# Hutschienenmoped_24V.net
KiCad netlist of a schematic drawn in EAGLE
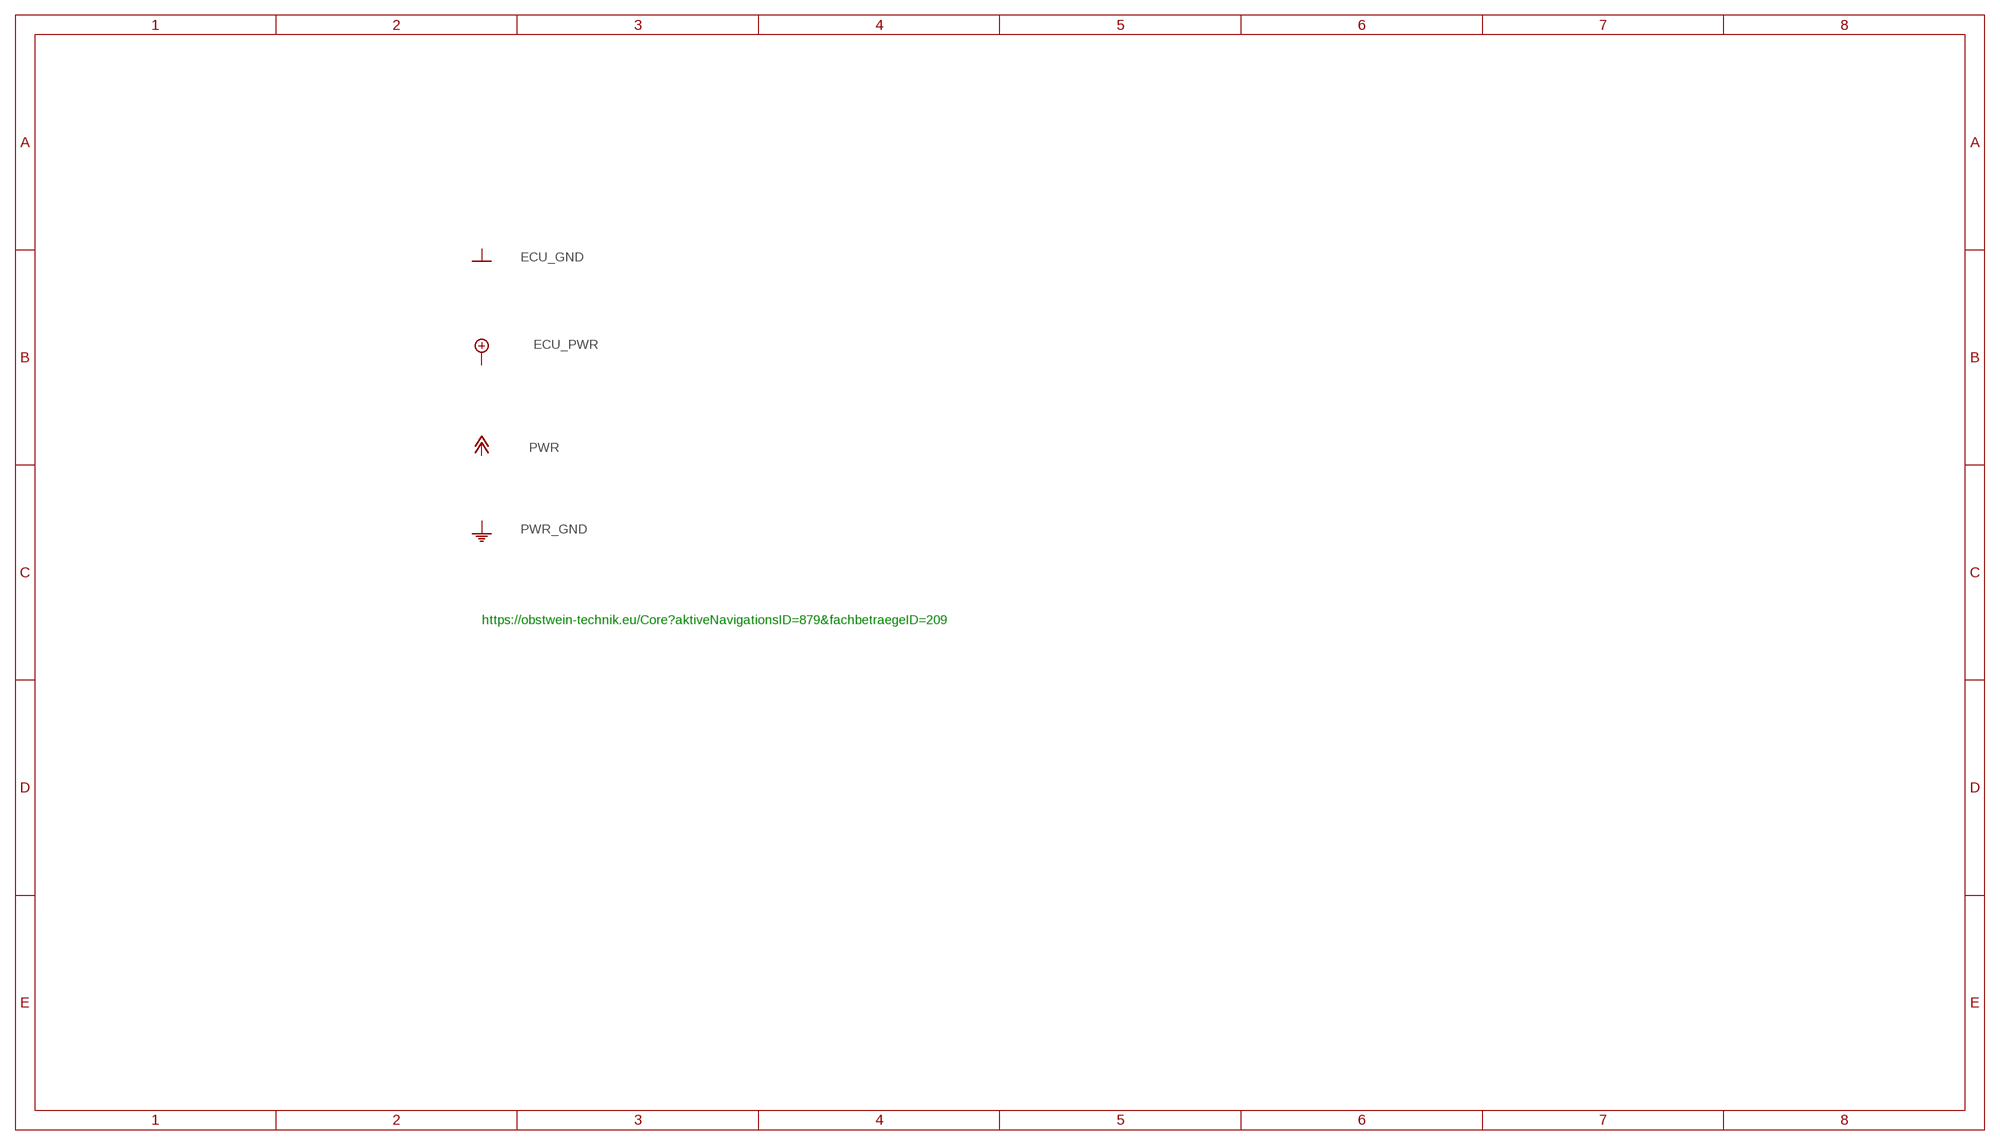
[diagram p0: schematic, sheet 1]
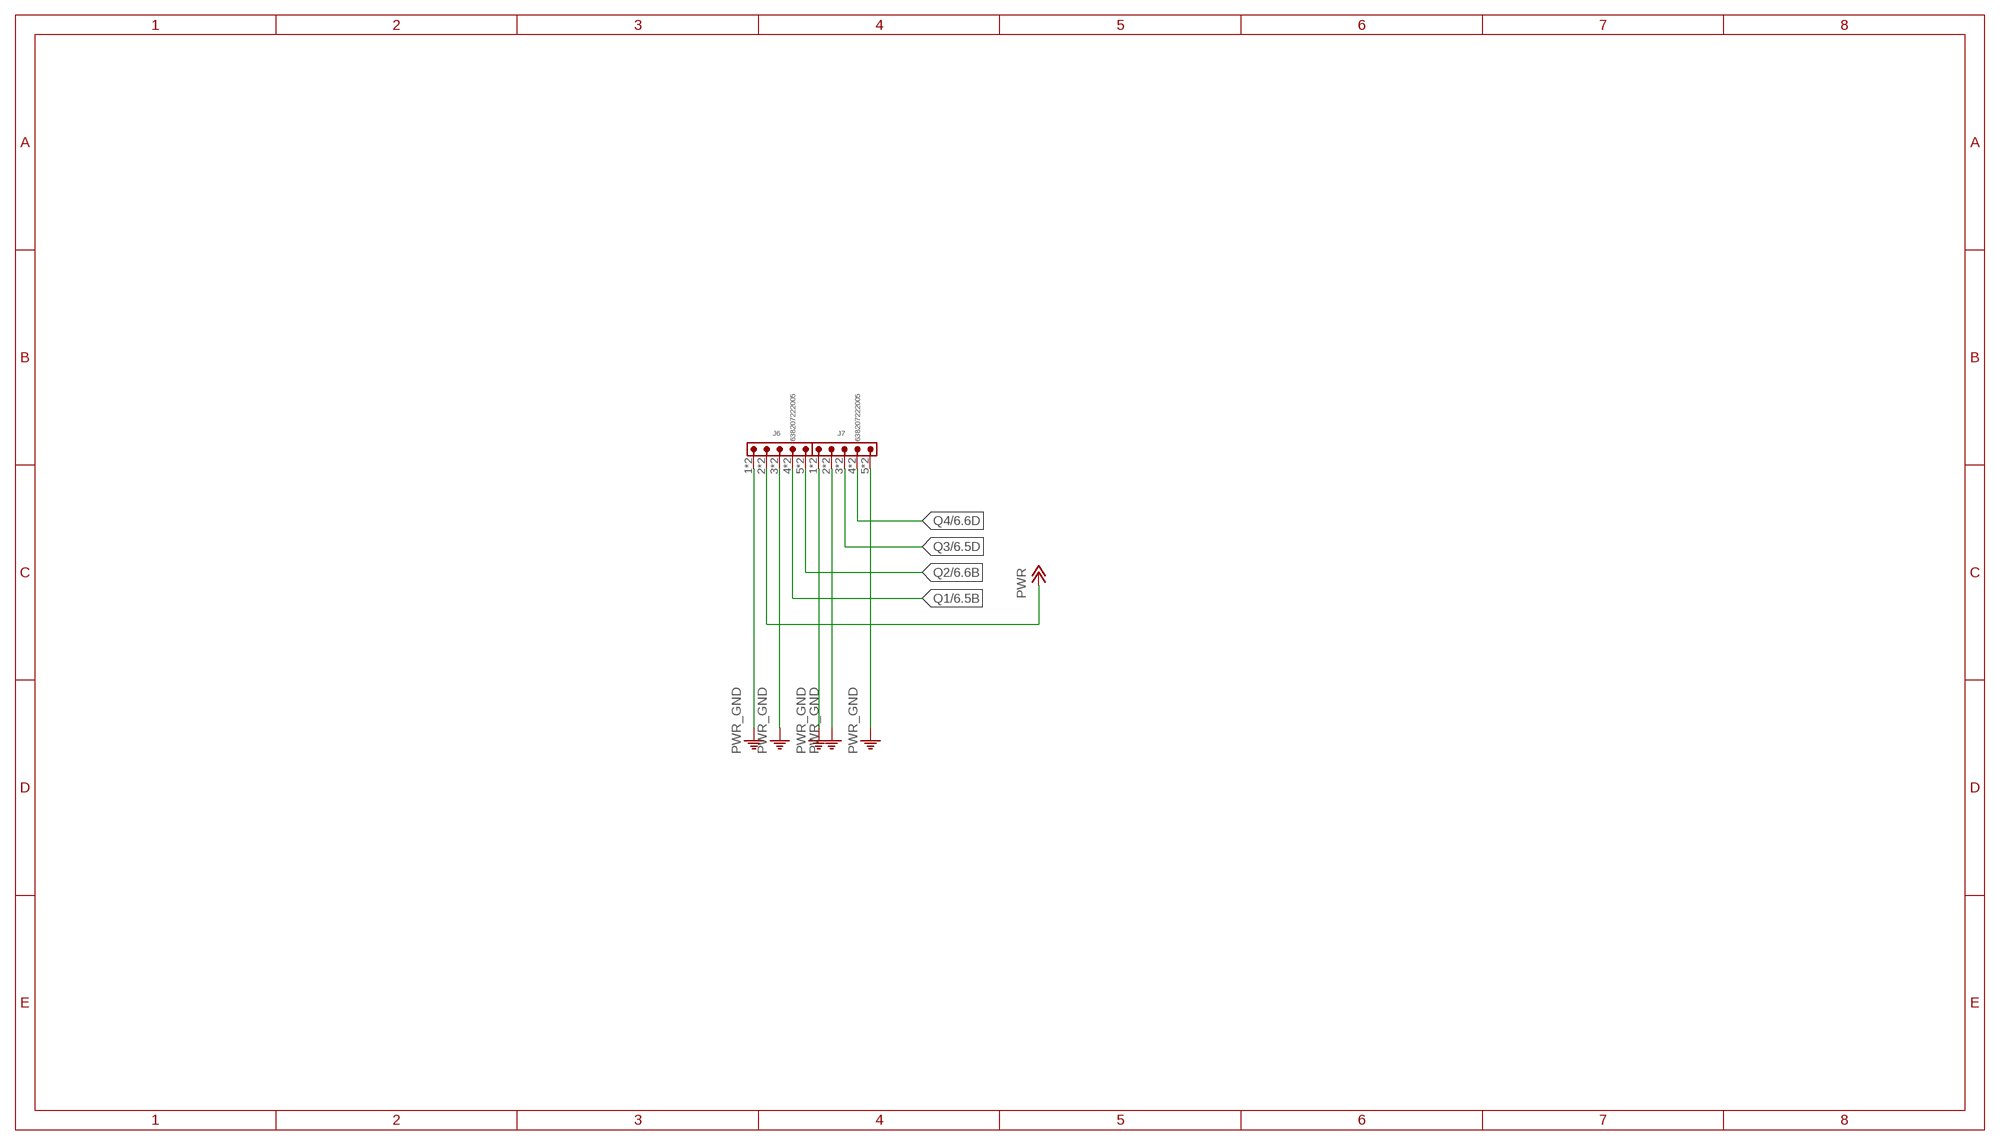
[diagram p1: schematic, sheet 2]
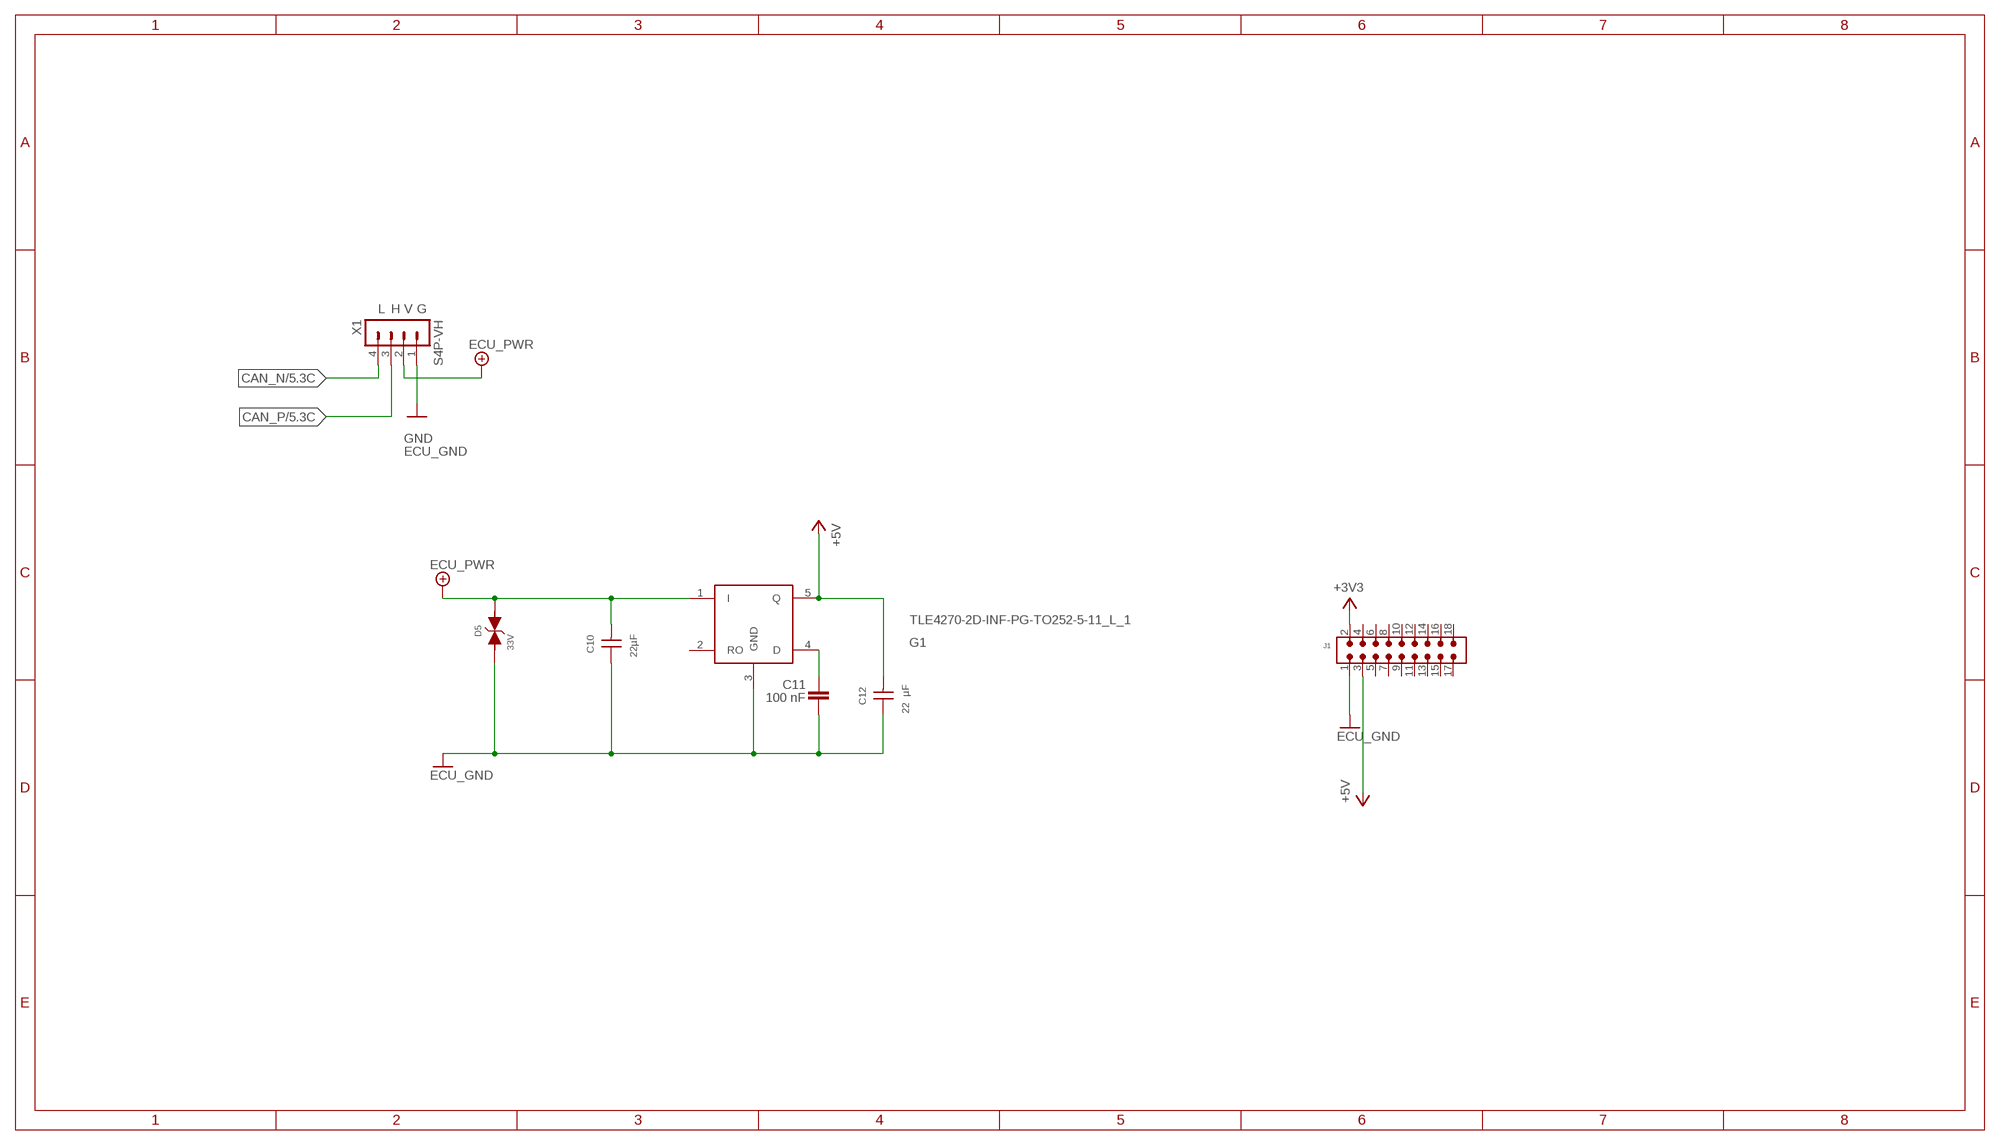
[diagram p2: schematic, sheet 3]
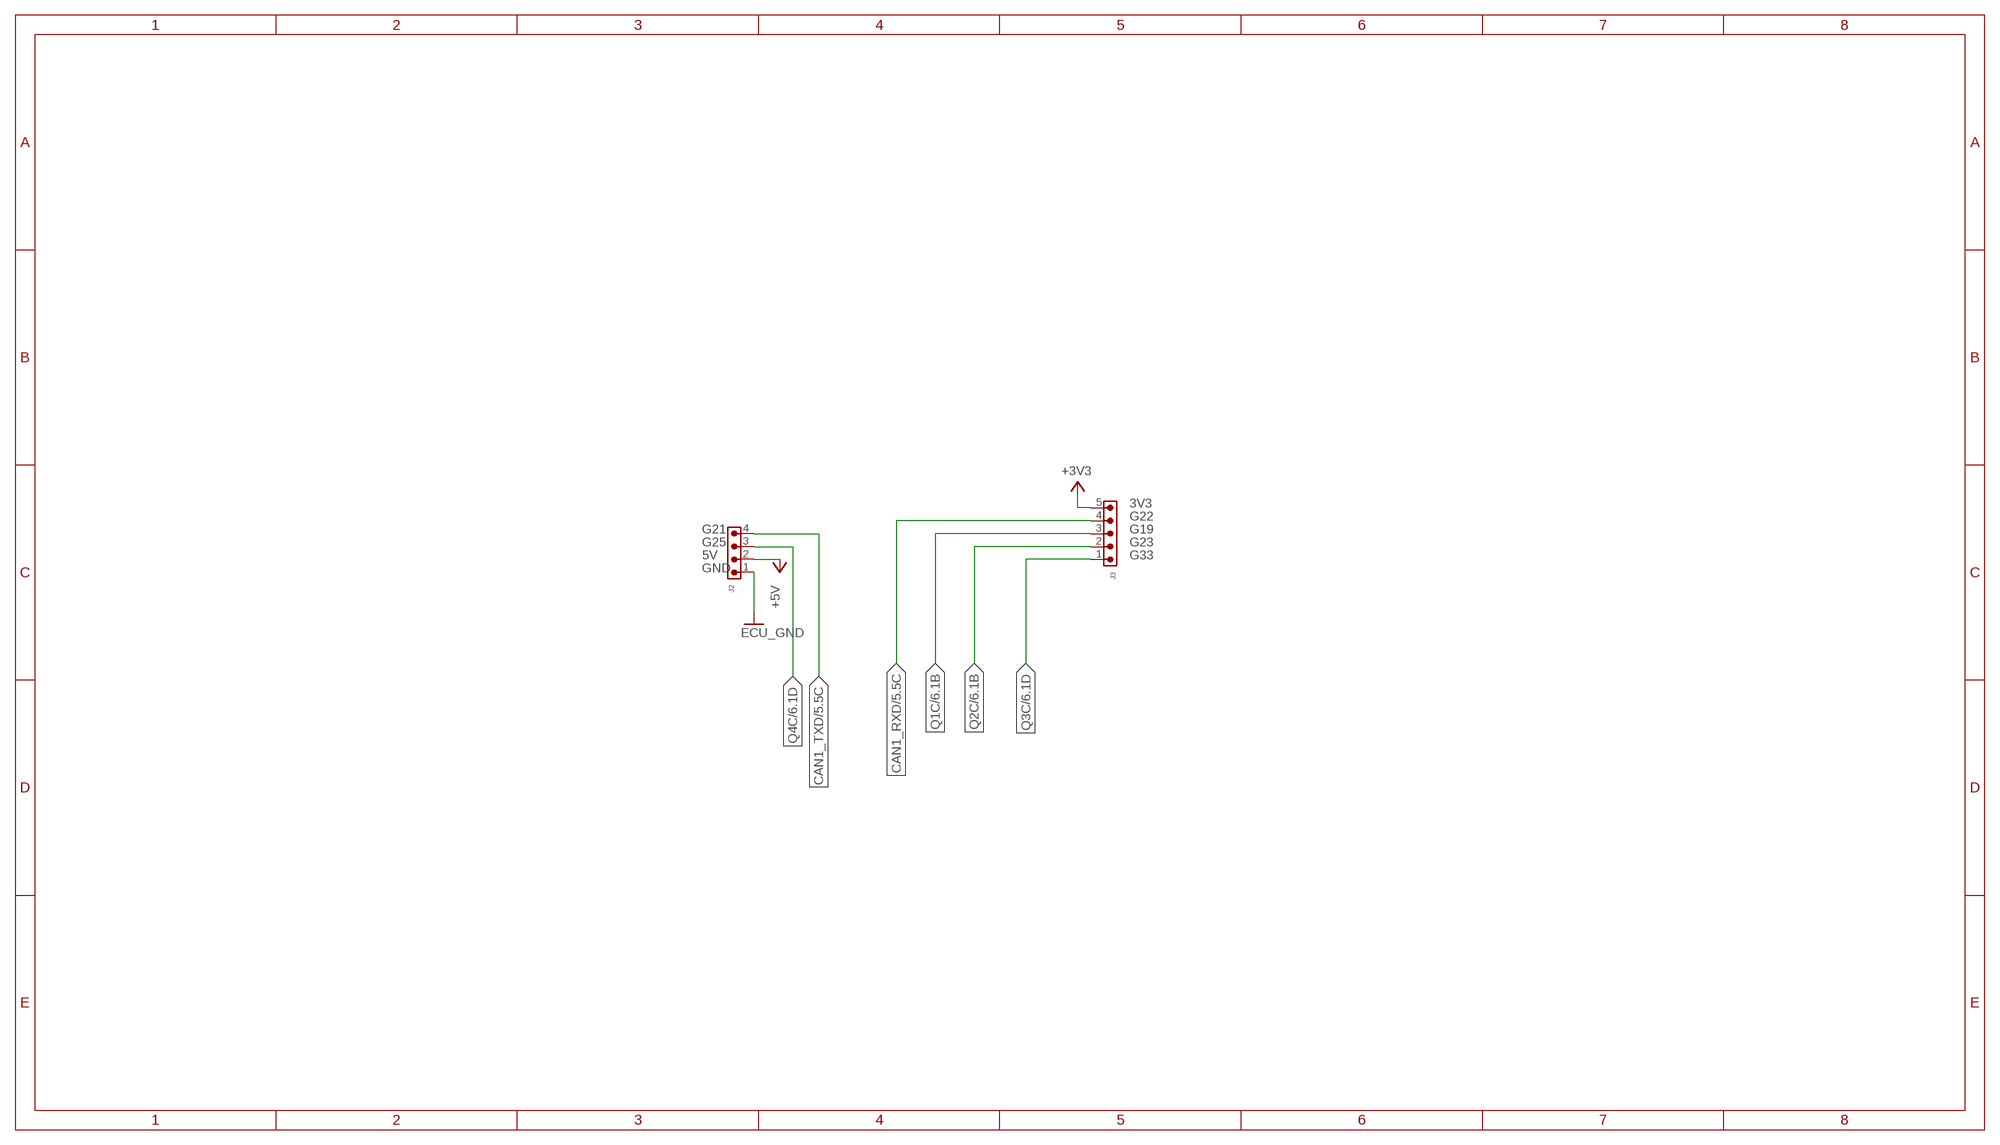
[diagram p3: schematic, sheet 4]
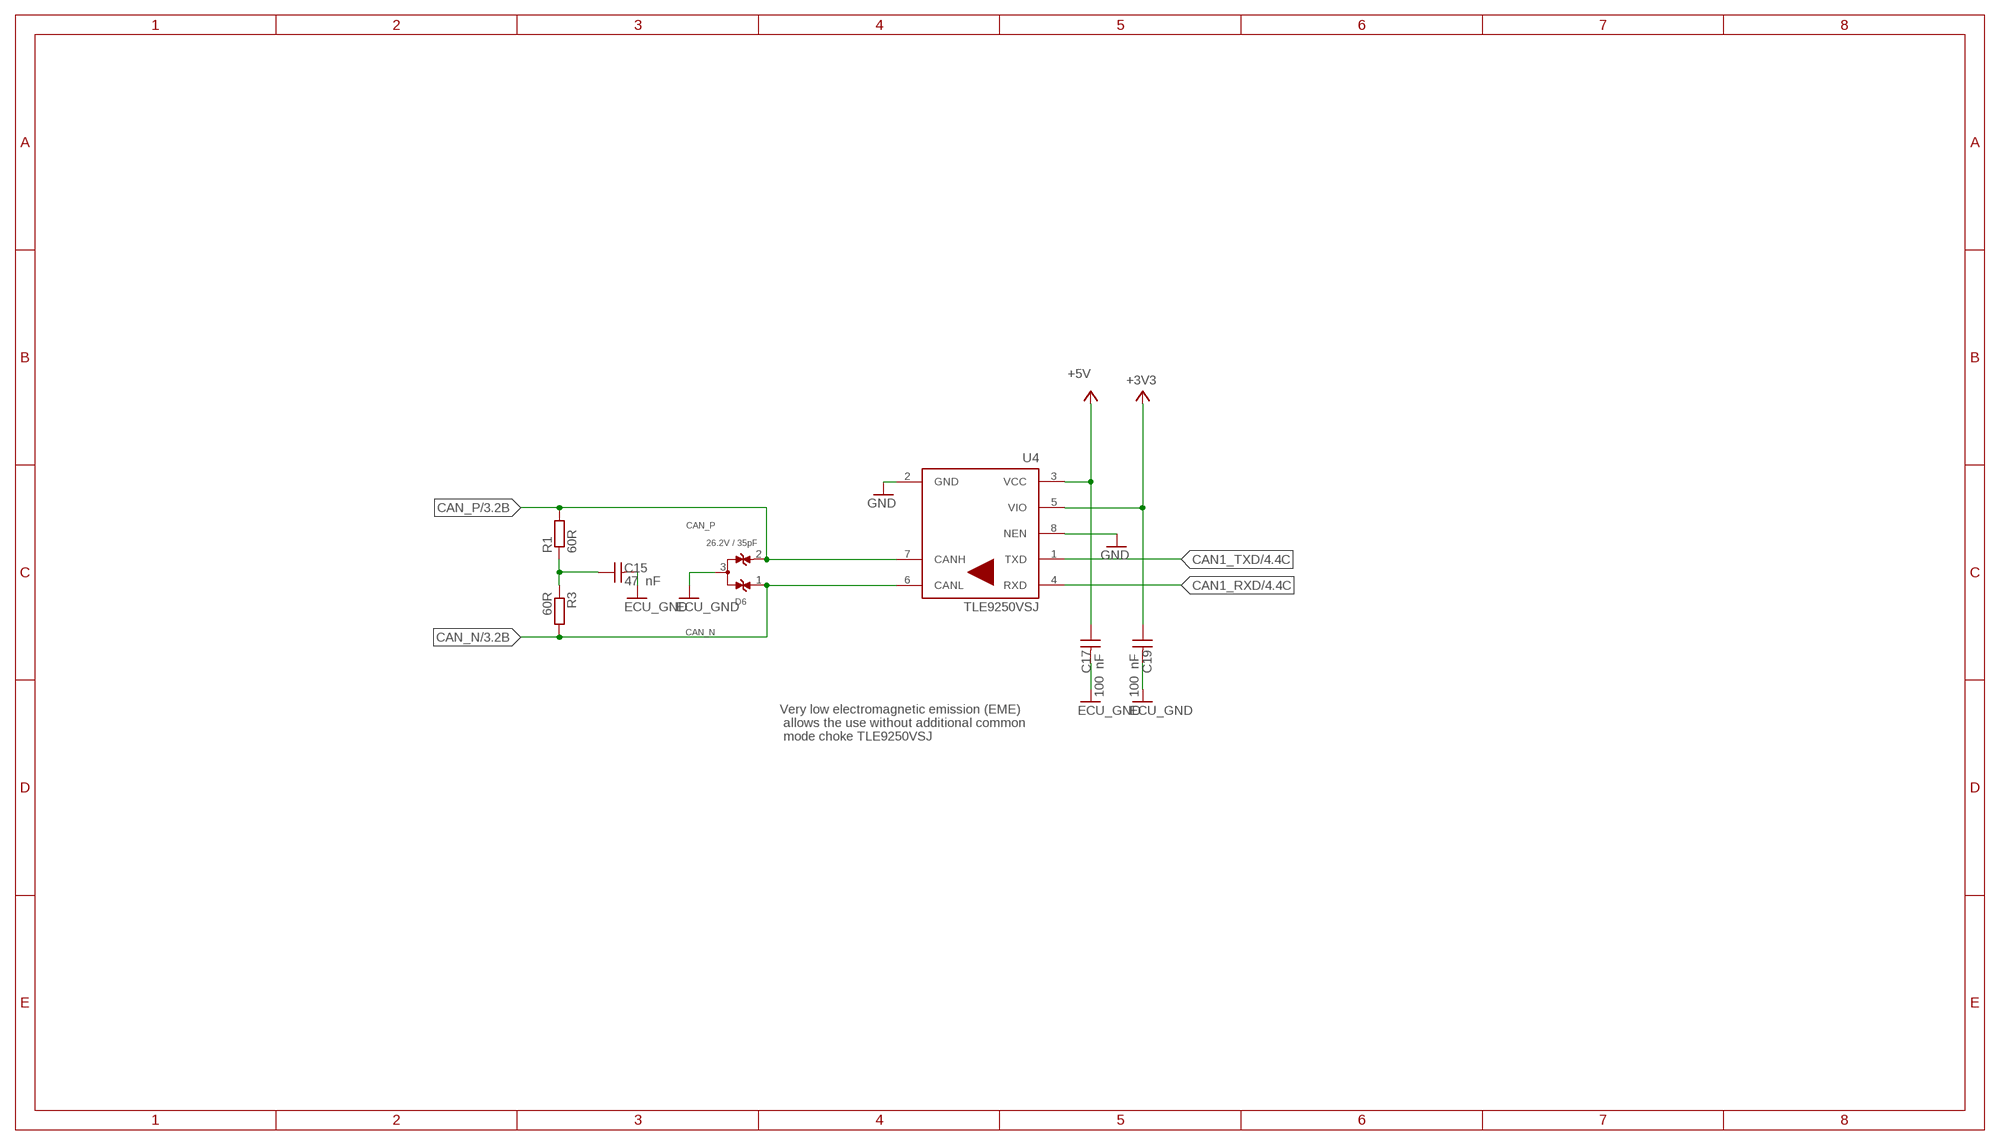
[diagram p4: schematic, sheet 5]
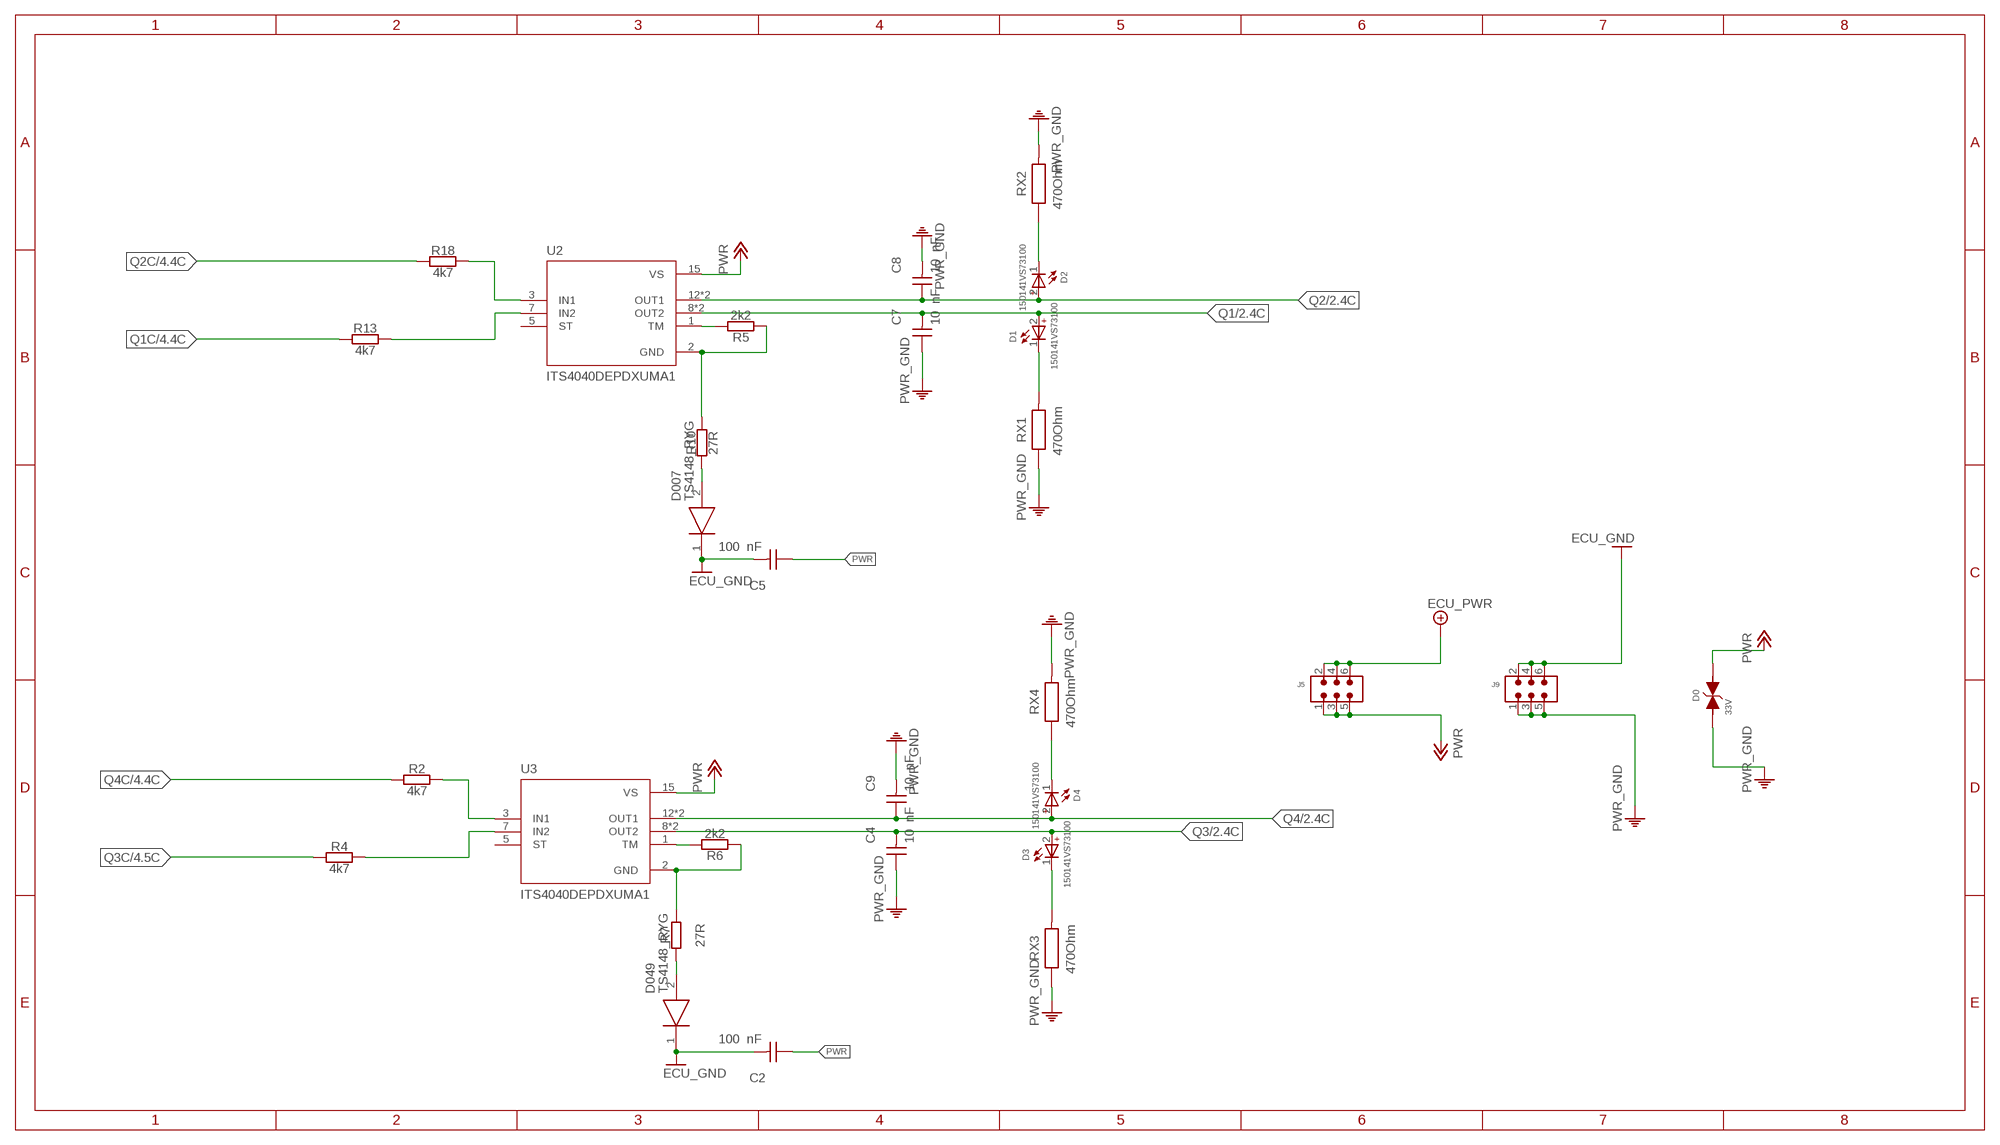
[diagram p5: schematic, sheet 6]

(export (version "E")
  (design (tool "Eeschema 10.0.6"))
  (components
    (comp (ref "C10")
      (value "22µF")
      (footprint "eagle-import:WCAP-CSGP_1210_H2.5")
      (libsource (lib "eagle-import") (part "WCAP-CSGP_1210_H2.5_25V(DC)_885012109014"))
    )
    (comp (ref "C11")
      (value "100 nF")
      (footprint "eagle-import:WCAP-CSGP_0402")
      (libsource (lib "eagle-import") (part "WCAP-CSGP_0402_16V(DC)_885012205037"))
    )
    (comp (ref "C12")
      (value "22 µF")
      (footprint "eagle-import:WCAP-CSGP_0805_H1.25_R")
      (libsource (lib "eagle-import") (part "WCAP-CSGP_0805_H1.25_10V(DC)_885012107011"))
    )
    (comp (ref "D5")
      (value "33V")
      (footprint "eagle-import:WE-TVSP_DO-214AB_BIDIRECTIONAL")
      (libsource (lib "eagle-import") (part "WE-TVSP_DO-214AB_3000W_BI_824551331"))
    )
    (comp (ref "G1")
      (value "TLE4270-2D-INF-PG-TO252-5-11_L_1")
      (footprint "eagle-import:INF-PG-TO252-5-11_L_1PRIMARY")
      (libsource (lib "eagle-import") (part "TLE4270-2D-INF-PG-TO252-5-11_L_1"))
    )
    (comp (ref "J1")
      (value "6130XX21121_61301821121")
      (footprint "eagle-import:61301821121")
      (libsource (lib "eagle-import") (part "6130XX21121_61301821121"))
    )
    (comp (ref "X1")
      (value "S4P-VH")
      (footprint "eagle-import:S4P-VH")
      (libsource (lib "eagle-import") (part "S4P-VH"))
    )
    (comp (ref "J2")
      (value "6130XX11121_61300411121")
      (footprint "eagle-import:61300411121")
      (libsource (lib "eagle-import") (part "6130XX11121_61300411121"))
    )
    (comp (ref "J3")
      (value "6130XX11121_61300511121")
      (footprint "eagle-import:61300511121")
      (libsource (lib "eagle-import") (part "6130XX11121_61300511121"))
    )
    (comp (ref "C15")
      (value "47 nF")
      (footprint "eagle-import:WCAP-CSGP_0805_H0.8_R")
      (libsource (lib "eagle-import") (part "WCAP-CSGP_0805_H0.8_50V(DC)_R_885012207096"))
    )
    (comp (ref "C17")
      (value "100 nF")
      (footprint "eagle-import:WCAP-CSGP_0805_H0.8_R")
      (libsource (lib "eagle-import") (part "WCAP-CSGP_0805_H0.8_50V(DC)_R_885012207098"))
    )
    (comp (ref "C19")
      (value "100 nF")
      (footprint "eagle-import:WCAP-CSGP_0805_H0.8_R")
      (libsource (lib "eagle-import") (part "WCAP-CSGP_0805_H0.8_50V(DC)_R_885012207098"))
    )
    (comp (ref "D6")
      (value "26.2V / 35pF")
      (footprint "eagle-import:WE-TVS_SOT23-3L")
      (libsource (lib "eagle-import") (part "WE-TVS_SOT23-3L_824098024"))
    )
    (comp (ref "R1")
      (value "60R")
      (footprint "eagle-import:R0805")
      (libsource (lib "eagle-import") (part "R-EU_R0805"))
    )
    (comp (ref "R3")
      (value "60R")
      (footprint "eagle-import:R0805")
      (libsource (lib "eagle-import") (part "R-EU_R0805"))
    )
    (comp (ref "U4")
      (value "TLE9250VSJ")
      (footprint "eagle-import:SOIC127P602X173-8N-V")
      (libsource (lib "eagle-import") (part "TLE9250VSJ"))
    )
    (comp (ref "C2")
      (value "100 nF")
      (footprint "eagle-import:WCAP-CSGP_0805_H0.8_R")
      (libsource (lib "eagle-import") (part "WCAP-CSGP_0805_H0.8_50V(DC)_R_885012207098"))
    )
    (comp (ref "C4")
      (value "10 nF")
      (footprint "eagle-import:WCAP-CSGP_0805_H0.8_R")
      (libsource (lib "eagle-import") (part "WCAP-CSGP_0805_H0.8_50V(DC)_R_885012207092"))
    )
    (comp (ref "C5")
      (value "100 nF")
      (footprint "eagle-import:WCAP-CSGP_0805_H0.8_R")
      (libsource (lib "eagle-import") (part "WCAP-CSGP_0805_H0.8_50V(DC)_R_885012207098"))
    )
    (comp (ref "C7")
      (value "10 nF")
      (footprint "eagle-import:WCAP-CSGP_0805_H0.8_R")
      (libsource (lib "eagle-import") (part "WCAP-CSGP_0805_H0.8_50V(DC)_R_885012207092"))
    )
    (comp (ref "C8")
      (value "10 nF")
      (footprint "eagle-import:WCAP-CSGP_0805_H0.8_R")
      (libsource (lib "eagle-import") (part "WCAP-CSGP_0805_H0.8_50V(DC)_R_885012207092"))
    )
    (comp (ref "C9")
      (value "10 nF")
      (footprint "eagle-import:WCAP-CSGP_0805_H0.8_R")
      (libsource (lib "eagle-import") (part "WCAP-CSGP_0805_H0.8_50V(DC)_R_885012207092"))
    )
    (comp (ref "D0")
      (value "33V")
      (footprint "eagle-import:WE-TVSP_DO-214AB_BIDIRECTIONAL")
      (libsource (lib "eagle-import") (part "WE-TVSP_DO-214AB_3000W_BI_824551331"))
    )
    (comp (ref "D1")
      (value "150141VS73100")
      (footprint "eagle-import:WL-SMTW_3528")
      (libsource (lib "eagle-import") (part "WL-SMTW_3528_150141VS73100"))
    )
    (comp (ref "D2")
      (value "150141VS73100")
      (footprint "eagle-import:WL-SMTW_3528")
      (libsource (lib "eagle-import") (part "WL-SMTW_3528_150141VS73100"))
    )
    (comp (ref "D3")
      (value "150141VS73100")
      (footprint "eagle-import:WL-SMTW_3528")
      (libsource (lib "eagle-import") (part "WL-SMTW_3528_150141VS73100"))
    )
    (comp (ref "D4")
      (value "150141VS73100")
      (footprint "eagle-import:WL-SMTW_3528")
      (libsource (lib "eagle-import") (part "WL-SMTW_3528_150141VS73100"))
    )
    (comp (ref "D007")
      (value "TS4148_RYG")
      (footprint "eagle-import:DIOC2012X95N")
      (fields
        (field (name "MANUFACTURER_PART_NUMBER") "TS4148 RYG")
        (field (name "MOUSER_PART_NUMBER") "821-TS4148RYG")
      )
      (libsource (lib "eagle-import") (part "TS4148_RYG"))
    )
    (comp (ref "D049")
      (value "TS4148_RYG")
      (footprint "eagle-import:DIOC2012X95N")
      (fields
        (field (name "MANUFACTURER_PART_NUMBER") "TS4148 RYG")
        (field (name "MOUSER_PART_NUMBER") "821-TS4148RYG")
      )
      (libsource (lib "eagle-import") (part "TS4148_RYG"))
    )
    (comp (ref "J5")
      (value "6130XX21121_61300621121")
      (footprint "eagle-import:61300621121")
      (libsource (lib "eagle-import") (part "6130XX21121_61300621121"))
    )
    (comp (ref "J9")
      (value "6130XX21121_61300621121")
      (footprint "eagle-import:61300621121")
      (libsource (lib "eagle-import") (part "6130XX21121_61300621121"))
    )
    (comp (ref "R2")
      (value "4k7")
      (footprint "eagle-import:R0805")
      (libsource (lib "eagle-import") (part "R-EU_R0805"))
    )
    (comp (ref "R4")
      (value "4k7")
      (footprint "eagle-import:R0805")
      (libsource (lib "eagle-import") (part "R-EU_R0805"))
    )
    (comp (ref "R5")
      (value "2k2")
      (footprint "eagle-import:R0805")
      (libsource (lib "eagle-import") (part "R-EU_R0805"))
    )
    (comp (ref "R6")
      (value "2k2")
      (footprint "eagle-import:R0805")
      (libsource (lib "eagle-import") (part "R-EU_R0805"))
    )
    (comp (ref "R7")
      (value "27R")
      (footprint "eagle-import:R0805")
      (libsource (lib "eagle-import") (part "R-EU_R0805"))
    )
    (comp (ref "R10")
      (value "27R")
      (footprint "eagle-import:R0805")
      (libsource (lib "eagle-import") (part "R-EU_R0805"))
    )
    (comp (ref "R13")
      (value "4k7")
      (footprint "eagle-import:R0805")
      (libsource (lib "eagle-import") (part "R-EU_R0805"))
    )
    (comp (ref "R18")
      (value "4k7")
      (footprint "eagle-import:R0805")
      (libsource (lib "eagle-import") (part "R-EU_R0805"))
    )
    (comp (ref "RX1")
      (value "470Ohm")
      (footprint "eagle-import:WRIS-KWKB_0612")
      (libsource (lib "eagle-import") (part "WRIS-KWKB_0612_561020132023"))
    )
    (comp (ref "RX2")
      (value "470Ohm")
      (footprint "eagle-import:WRIS-KWKB_0612")
      (libsource (lib "eagle-import") (part "WRIS-KWKB_0612_561020132023"))
    )
    (comp (ref "RX3")
      (value "470Ohm")
      (footprint "eagle-import:WRIS-KWKB_0612")
      (libsource (lib "eagle-import") (part "WRIS-KWKB_0612_561020132023"))
    )
    (comp (ref "RX4")
      (value "470Ohm")
      (footprint "eagle-import:WRIS-KWKB_0612")
      (libsource (lib "eagle-import") (part "WRIS-KWKB_0612_561020132023"))
    )
    (comp (ref "U2")
      (value "ITS4040DEPDXUMA1")
      (footprint "eagle-import:SOP65P600X115-15N")
      (fields
        (field (name "DIGI-KEY_PART_NUMBER") "ITS4040DEPDXUMA1TR-ND")
        (field (name "MF") "Infineon Technologies")
      )
      (libsource (lib "eagle-import") (part "ITS4040DEPDXUMA1"))
    )
    (comp (ref "U3")
      (value "ITS4040DEPDXUMA1")
      (footprint "eagle-import:SOP65P600X115-15N")
      (fields
        (field (name "DIGI-KEY_PART_NUMBER") "ITS4040DEPDXUMA1TR-ND")
        (field (name "MF") "Infineon Technologies")
      )
      (libsource (lib "eagle-import") (part "ITS4040DEPDXUMA1"))
    )
    (comp (ref "J6")
      (value "638207222005")
      (footprint "eagle-import:638207222005")
      (libsource (lib "eagle-import") (part "638207222005"))
    )
    (comp (ref "J7")
      (value "638207222005")
      (footprint "eagle-import:638207222005")
      (libsource (lib "eagle-import") (part "638207222005"))
    )
  )
  (nets
    (net (code "1") (name "+3V3") (class "Default")
      (node (ref "C19") (pin "1") (pinfunction "1_1") (pintype "passive"))
      (node (ref "J1") (pin "2") (pinfunction "2_2") (pintype "passive"))
      (node (ref "J3") (pin "5") (pinfunction "5_5") (pintype "passive"))
      (node (ref "U4") (pin "5") (pinfunction "VIO_5") (pintype "input"))
    )
    (net (code "2") (name "+5V") (class "Default")
      (node (ref "C12") (pin "2") (pinfunction "2_2") (pintype "passive"))
      (node (ref "C17") (pin "1") (pinfunction "1_1") (pintype "passive"))
      (node (ref "G1") (pin "5") (pinfunction "Q_5") (pintype "power_in"))
      (node (ref "J1") (pin "3") (pinfunction "3_3") (pintype "passive"))
      (node (ref "J2") (pin "2") (pinfunction "2_2") (pintype "passive"))
      (node (ref "U4") (pin "3") (pinfunction "VCC_3") (pintype "input"))
    )
    (net (code "3") (name "CAN1_RXD") (class "Default")
      (node (ref "J3") (pin "4") (pinfunction "4_4") (pintype "passive"))
      (node (ref "U4") (pin "4") (pinfunction "RXD_4") (pintype "output"))
    )
    (net (code "4") (name "CAN1_TXD") (class "Default")
      (node (ref "J2") (pin "4") (pinfunction "4_4") (pintype "passive"))
      (node (ref "U4") (pin "1") (pinfunction "TXD_1") (pintype "input"))
    )
    (net (code "5") (name "CAN_N") (class "Default")
      (node (ref "D6") (pin "1") (pinfunction "1_1") (pintype "passive"))
      (node (ref "R3") (pin "2") (pinfunction "2_2") (pintype "passive"))
      (node (ref "U4") (pin "6") (pinfunction "CANL_6") (pintype "bidirectional"))
      (node (ref "X1") (pin "4") (pinfunction "4_4") (pintype "passive"))
    )
    (net (code "6") (name "CAN_P") (class "Default")
      (node (ref "D6") (pin "2") (pinfunction "2_2") (pintype "passive"))
      (node (ref "R1") (pin "2") (pinfunction "2_2") (pintype "passive"))
      (node (ref "U4") (pin "7") (pinfunction "CANH_7") (pintype "bidirectional"))
      (node (ref "X1") (pin "3") (pinfunction "3_3") (pintype "passive"))
    )
    (net (code "7") (name "ECU_GND") (class "Default")
      (node (ref "C10") (pin "1") (pinfunction "1_1") (pintype "passive"))
      (node (ref "C11") (pin "2") (pinfunction "2_2") (pintype "passive"))
      (node (ref "C12") (pin "1") (pinfunction "1_1") (pintype "passive"))
      (node (ref "C15") (pin "2") (pinfunction "2_2") (pintype "passive"))
      (node (ref "C17") (pin "2") (pinfunction "2_2") (pintype "passive"))
      (node (ref "C19") (pin "2") (pinfunction "2_2") (pintype "passive"))
      (node (ref "C2") (pin "2") (pinfunction "2_2") (pintype "passive"))
      (node (ref "C5") (pin "2") (pinfunction "2_2") (pintype "passive"))
      (node (ref "D007") (pin "1") (pinfunction "K_1") (pintype "bidirectional"))
      (node (ref "D049") (pin "1") (pinfunction "K_1") (pintype "bidirectional"))
      (node (ref "D5") (pin "1") (pinfunction "1_1") (pintype "passive"))
      (node (ref "D6") (pin "3") (pinfunction "3_3") (pintype "passive"))
      (node (ref "G1") (pin "3") (pinfunction "GND_3") (pintype "power_in"))
      (node (ref "J1") (pin "1") (pinfunction "1_1") (pintype "passive"))
      (node (ref "J2") (pin "1") (pinfunction "1_1") (pintype "passive"))
      (node (ref "J9") (pin "2") (pinfunction "2_2") (pintype "passive"))
      (node (ref "J9") (pin "4") (pinfunction "4_4") (pintype "passive"))
      (node (ref "J9") (pin "6") (pinfunction "6_6") (pintype "passive"))
      (node (ref "U4") (pin "2") (pinfunction "GND_2") (pintype "power_in"))
      (node (ref "U4") (pin "8") (pinfunction "NEN_8") (pintype "input"))
      (node (ref "X1") (pin "1") (pinfunction "1_1") (pintype "passive"))
    )
    (net (code "8") (name "ECU_PWR") (class "Default")
      (node (ref "C10") (pin "2") (pinfunction "2_2") (pintype "passive"))
      (node (ref "D5") (pin "2") (pinfunction "2_2") (pintype "passive"))
      (node (ref "G1") (pin "1") (pinfunction "I_1") (pintype "power_in"))
      (node (ref "J5") (pin "2") (pinfunction "2_2") (pintype "passive"))
      (node (ref "J5") (pin "4") (pinfunction "4_4") (pintype "passive"))
      (node (ref "J5") (pin "6") (pinfunction "6_6") (pintype "passive"))
      (node (ref "X1") (pin "2") (pinfunction "2_2") (pintype "passive"))
    )
    (net (code "9") (name "Net-(C15-Pad1)") (class "Default")
      (node (ref "C15") (pin "1") (pinfunction "1_1") (pintype "passive"))
      (node (ref "R1") (pin "1") (pinfunction "1_1") (pintype "passive"))
      (node (ref "R3") (pin "1") (pinfunction "1_1") (pintype "passive"))
    )
    (net (code "10") (name "Net-(D1--)") (class "Default")
      (node (ref "D1") (pin "1") (pinfunction "-_1") (pintype "passive"))
      (node (ref "RX1") (pin "2") (pinfunction "2_2") (pintype "passive"))
    )
    (net (code "11") (name "Net-(D2--)") (class "Default")
      (node (ref "D2") (pin "1") (pinfunction "-_1") (pintype "passive"))
      (node (ref "RX2") (pin "1") (pinfunction "1_1") (pintype "passive"))
    )
    (net (code "12") (name "Net-(D3--)") (class "Default")
      (node (ref "D3") (pin "1") (pinfunction "-_1") (pintype "passive"))
      (node (ref "RX3") (pin "2") (pinfunction "2_2") (pintype "passive"))
    )
    (net (code "13") (name "Net-(D4--)") (class "Default")
      (node (ref "D4") (pin "1") (pinfunction "-_1") (pintype "passive"))
      (node (ref "RX4") (pin "1") (pinfunction "1_1") (pintype "passive"))
    )
    (net (code "14") (name "Net-(D007-A)") (class "Default")
      (node (ref "D007") (pin "2") (pinfunction "A_2") (pintype "bidirectional"))
      (node (ref "R10") (pin "1") (pinfunction "1_1") (pintype "passive"))
    )
    (net (code "15") (name "Net-(D049-A)") (class "Default")
      (node (ref "D049") (pin "2") (pinfunction "A_2") (pintype "bidirectional"))
      (node (ref "R7") (pin "1") (pinfunction "1_1") (pintype "passive"))
    )
    (net (code "16") (name "Net-(G1-D)") (class "Default")
      (node (ref "C11") (pin "1") (pinfunction "1_1") (pintype "passive"))
      (node (ref "G1") (pin "4") (pinfunction "D_4") (pintype "bidirectional"))
    )
    (net (code "17") (name "Net-(U2-GND)") (class "Default")
      (node (ref "R10") (pin "2") (pinfunction "2_2") (pintype "passive"))
      (node (ref "R5") (pin "1") (pinfunction "1_1") (pintype "passive"))
      (node (ref "U2") (pin "2") (pinfunction "GND_2") (pintype "power_in"))
    )
    (net (code "18") (name "Net-(U2-IN1)") (class "Default")
      (node (ref "R18") (pin "2") (pinfunction "2_2") (pintype "passive"))
      (node (ref "U2") (pin "3") (pinfunction "IN1_3") (pintype "input"))
    )
    (net (code "19") (name "Net-(U2-IN2)") (class "Default")
      (node (ref "R13") (pin "2") (pinfunction "2_2") (pintype "passive"))
      (node (ref "U2") (pin "7") (pinfunction "IN2_7") (pintype "input"))
    )
    (net (code "20") (name "Net-(U2-TM)") (class "Default")
      (node (ref "R5") (pin "2") (pinfunction "2_2") (pintype "passive"))
      (node (ref "U2") (pin "1") (pinfunction "TM_1") (pintype "passive"))
    )
    (net (code "21") (name "Net-(U3-GND)") (class "Default")
      (node (ref "R6") (pin "1") (pinfunction "1_1") (pintype "passive"))
      (node (ref "R7") (pin "2") (pinfunction "2_2") (pintype "passive"))
      (node (ref "U3") (pin "2") (pinfunction "GND_2") (pintype "power_in"))
    )
    (net (code "22") (name "Net-(U3-IN1)") (class "Default")
      (node (ref "R2") (pin "2") (pinfunction "2_2") (pintype "passive"))
      (node (ref "U3") (pin "3") (pinfunction "IN1_3") (pintype "input"))
    )
    (net (code "23") (name "Net-(U3-IN2)") (class "Default")
      (node (ref "R4") (pin "2") (pinfunction "2_2") (pintype "passive"))
      (node (ref "U3") (pin "7") (pinfunction "IN2_7") (pintype "input"))
    )
    (net (code "24") (name "Net-(U3-TM)") (class "Default")
      (node (ref "R6") (pin "2") (pinfunction "2_2") (pintype "passive"))
      (node (ref "U3") (pin "1") (pinfunction "TM_1") (pintype "passive"))
    )
    (net (code "25") (name "PWR") (class "Default")
      (node (ref "C2") (pin "1") (pinfunction "1_1") (pintype "passive"))
      (node (ref "C5") (pin "1") (pinfunction "1_1") (pintype "passive"))
      (node (ref "D0") (pin "2") (pinfunction "2_2") (pintype "passive"))
      (node (ref "J5") (pin "1") (pinfunction "1_1") (pintype "passive"))
      (node (ref "J5") (pin "3") (pinfunction "3_3") (pintype "passive"))
      (node (ref "J5") (pin "5") (pinfunction "5_5") (pintype "passive"))
      (node (ref "J6") (pin "2") (pinfunction "2_2") (pintype "passive"))
      (node (ref "J6") (pin "A2") (pinfunction "2_A2") (pintype "passive"))
      (node (ref "U2") (pin "15") (pinfunction "VS_15") (pintype "power_in"))
      (node (ref "U3") (pin "15") (pinfunction "VS_15") (pintype "power_in"))
    )
    (net (code "26") (name "PWR_GND") (class "Default")
      (node (ref "C4") (pin "1") (pinfunction "1_1") (pintype "passive"))
      (node (ref "C7") (pin "1") (pinfunction "1_1") (pintype "passive"))
      (node (ref "C8") (pin "2") (pinfunction "2_2") (pintype "passive"))
      (node (ref "C9") (pin "2") (pinfunction "2_2") (pintype "passive"))
      (node (ref "D0") (pin "1") (pinfunction "1_1") (pintype "passive"))
      (node (ref "J6") (pin "1") (pinfunction "1_1") (pintype "passive"))
      (node (ref "J6") (pin "3") (pinfunction "3_3") (pintype "passive"))
      (node (ref "J6") (pin "A1") (pinfunction "1_A1") (pintype "passive"))
      (node (ref "J6") (pin "A3") (pinfunction "3_A3") (pintype "passive"))
      (node (ref "J7") (pin "1") (pinfunction "1_1") (pintype "passive"))
      (node (ref "J7") (pin "2") (pinfunction "2_2") (pintype "passive"))
      (node (ref "J7") (pin "5") (pinfunction "5_5") (pintype "passive"))
      (node (ref "J7") (pin "A1") (pinfunction "1_A1") (pintype "passive"))
      (node (ref "J7") (pin "A2") (pinfunction "2_A2") (pintype "passive"))
      (node (ref "J7") (pin "A5") (pinfunction "5_A5") (pintype "passive"))
      (node (ref "J9") (pin "1") (pinfunction "1_1") (pintype "passive"))
      (node (ref "J9") (pin "3") (pinfunction "3_3") (pintype "passive"))
      (node (ref "J9") (pin "5") (pinfunction "5_5") (pintype "passive"))
      (node (ref "RX1") (pin "1") (pinfunction "1_1") (pintype "passive"))
      (node (ref "RX2") (pin "2") (pinfunction "2_2") (pintype "passive"))
      (node (ref "RX3") (pin "1") (pinfunction "1_1") (pintype "passive"))
      (node (ref "RX4") (pin "2") (pinfunction "2_2") (pintype "passive"))
    )
    (net (code "27") (name "Q1") (class "Default")
      (node (ref "C7") (pin "2") (pinfunction "2_2") (pintype "passive"))
      (node (ref "D1") (pin "2") (pinfunction "+_2") (pintype "passive"))
      (node (ref "J6") (pin "4") (pinfunction "4_4") (pintype "passive"))
      (node (ref "J6") (pin "A4") (pinfunction "4_A4") (pintype "passive"))
      (node (ref "U2") (pin "10") (pinfunction "OUT2_10") (pintype "output"))
      (node (ref "U2") (pin "8") (pinfunction "OUT2_8") (pintype "output"))
    )
    (net (code "28") (name "Q1C") (class "Default")
      (node (ref "J3") (pin "3") (pinfunction "3_3") (pintype "passive"))
      (node (ref "R13") (pin "1") (pinfunction "1_1") (pintype "passive"))
    )
    (net (code "29") (name "Q2") (class "Default")
      (node (ref "C8") (pin "1") (pinfunction "1_1") (pintype "passive"))
      (node (ref "D2") (pin "2") (pinfunction "+_2") (pintype "passive"))
      (node (ref "J6") (pin "5") (pinfunction "5_5") (pintype "passive"))
      (node (ref "J6") (pin "A5") (pinfunction "5_A5") (pintype "passive"))
      (node (ref "U2") (pin "12") (pinfunction "OUT1_12") (pintype "output"))
      (node (ref "U2") (pin "14") (pinfunction "OUT1_14") (pintype "output"))
    )
    (net (code "30") (name "Q2C") (class "Default")
      (node (ref "J3") (pin "2") (pinfunction "2_2") (pintype "passive"))
      (node (ref "R18") (pin "1") (pinfunction "1_1") (pintype "passive"))
    )
    (net (code "31") (name "Q3") (class "Default")
      (node (ref "C4") (pin "2") (pinfunction "2_2") (pintype "passive"))
      (node (ref "D3") (pin "2") (pinfunction "+_2") (pintype "passive"))
      (node (ref "J7") (pin "3") (pinfunction "3_3") (pintype "passive"))
      (node (ref "J7") (pin "A3") (pinfunction "3_A3") (pintype "passive"))
      (node (ref "U3") (pin "10") (pinfunction "OUT2_10") (pintype "output"))
      (node (ref "U3") (pin "8") (pinfunction "OUT2_8") (pintype "output"))
    )
    (net (code "32") (name "Q3C") (class "Default")
      (node (ref "J3") (pin "1") (pinfunction "1_1") (pintype "passive"))
      (node (ref "R4") (pin "1") (pinfunction "1_1") (pintype "passive"))
    )
    (net (code "33") (name "Q4") (class "Default")
      (node (ref "C9") (pin "1") (pinfunction "1_1") (pintype "passive"))
      (node (ref "D4") (pin "2") (pinfunction "+_2") (pintype "passive"))
      (node (ref "J7") (pin "4") (pinfunction "4_4") (pintype "passive"))
      (node (ref "J7") (pin "A4") (pinfunction "4_A4") (pintype "passive"))
      (node (ref "U3") (pin "12") (pinfunction "OUT1_12") (pintype "output"))
      (node (ref "U3") (pin "14") (pinfunction "OUT1_14") (pintype "output"))
    )
    (net (code "34") (name "Q4C") (class "Default")
      (node (ref "J2") (pin "3") (pinfunction "3_3") (pintype "passive"))
      (node (ref "R2") (pin "1") (pinfunction "1_1") (pintype "passive"))
    )
    (net (code "35") (name "unconnected-(G1-RO-Pad2)") (class "Default")
      (node (ref "G1") (pin "2") (pinfunction "RO_2") (pintype "output"))
    )
    (net (code "36") (name "unconnected-(J1-Pad4)") (class "Default")
      (node (ref "J1") (pin "4") (pinfunction "4_4") (pintype "passive"))
    )
    (net (code "37") (name "unconnected-(J1-Pad5)") (class "Default")
      (node (ref "J1") (pin "5") (pinfunction "5_5") (pintype "passive"))
    )
    (net (code "38") (name "unconnected-(J1-Pad6)") (class "Default")
      (node (ref "J1") (pin "6") (pinfunction "6_6") (pintype "passive"))
    )
    (net (code "39") (name "unconnected-(J1-Pad7)") (class "Default")
      (node (ref "J1") (pin "7") (pinfunction "7_7") (pintype "passive"))
    )
    (net (code "40") (name "unconnected-(J1-Pad8)") (class "Default")
      (node (ref "J1") (pin "8") (pinfunction "8_8") (pintype "passive"))
    )
    (net (code "41") (name "unconnected-(J1-Pad9)") (class "Default")
      (node (ref "J1") (pin "9") (pinfunction "9_9") (pintype "passive"))
    )
    (net (code "42") (name "unconnected-(J1-Pad10)") (class "Default")
      (node (ref "J1") (pin "10") (pinfunction "10_10") (pintype "passive"))
    )
    (net (code "43") (name "unconnected-(J1-Pad11)") (class "Default")
      (node (ref "J1") (pin "11") (pinfunction "11_11") (pintype "passive"))
    )
    (net (code "44") (name "unconnected-(J1-Pad12)") (class "Default")
      (node (ref "J1") (pin "12") (pinfunction "12_12") (pintype "passive"))
    )
    (net (code "45") (name "unconnected-(J1-Pad13)") (class "Default")
      (node (ref "J1") (pin "13") (pinfunction "13_13") (pintype "passive"))
    )
    (net (code "46") (name "unconnected-(J1-Pad14)") (class "Default")
      (node (ref "J1") (pin "14") (pinfunction "14_14") (pintype "passive"))
    )
    (net (code "47") (name "unconnected-(J1-Pad15)") (class "Default")
      (node (ref "J1") (pin "15") (pinfunction "15_15") (pintype "passive"))
    )
    (net (code "48") (name "unconnected-(J1-Pad16)") (class "Default")
      (node (ref "J1") (pin "16") (pinfunction "16_16") (pintype "passive"))
    )
    (net (code "49") (name "unconnected-(J1-Pad17)") (class "Default")
      (node (ref "J1") (pin "17") (pinfunction "17_17") (pintype "passive"))
    )
    (net (code "50") (name "unconnected-(J1-Pad18)") (class "Default")
      (node (ref "J1") (pin "18") (pinfunction "18_18") (pintype "passive"))
    )
    (net (code "51") (name "unconnected-(U2-ST-Pad5)") (class "Default")
      (node (ref "U2") (pin "5") (pinfunction "ST_5") (pintype "input"))
    )
    (net (code "52") (name "unconnected-(U3-ST-Pad5)") (class "Default")
      (node (ref "U3") (pin "5") (pinfunction "ST_5") (pintype "input"))
    )
  )
)
